# BCD_Counter_1_1.net
KiCad netlist of a schematic drawn in EAGLE
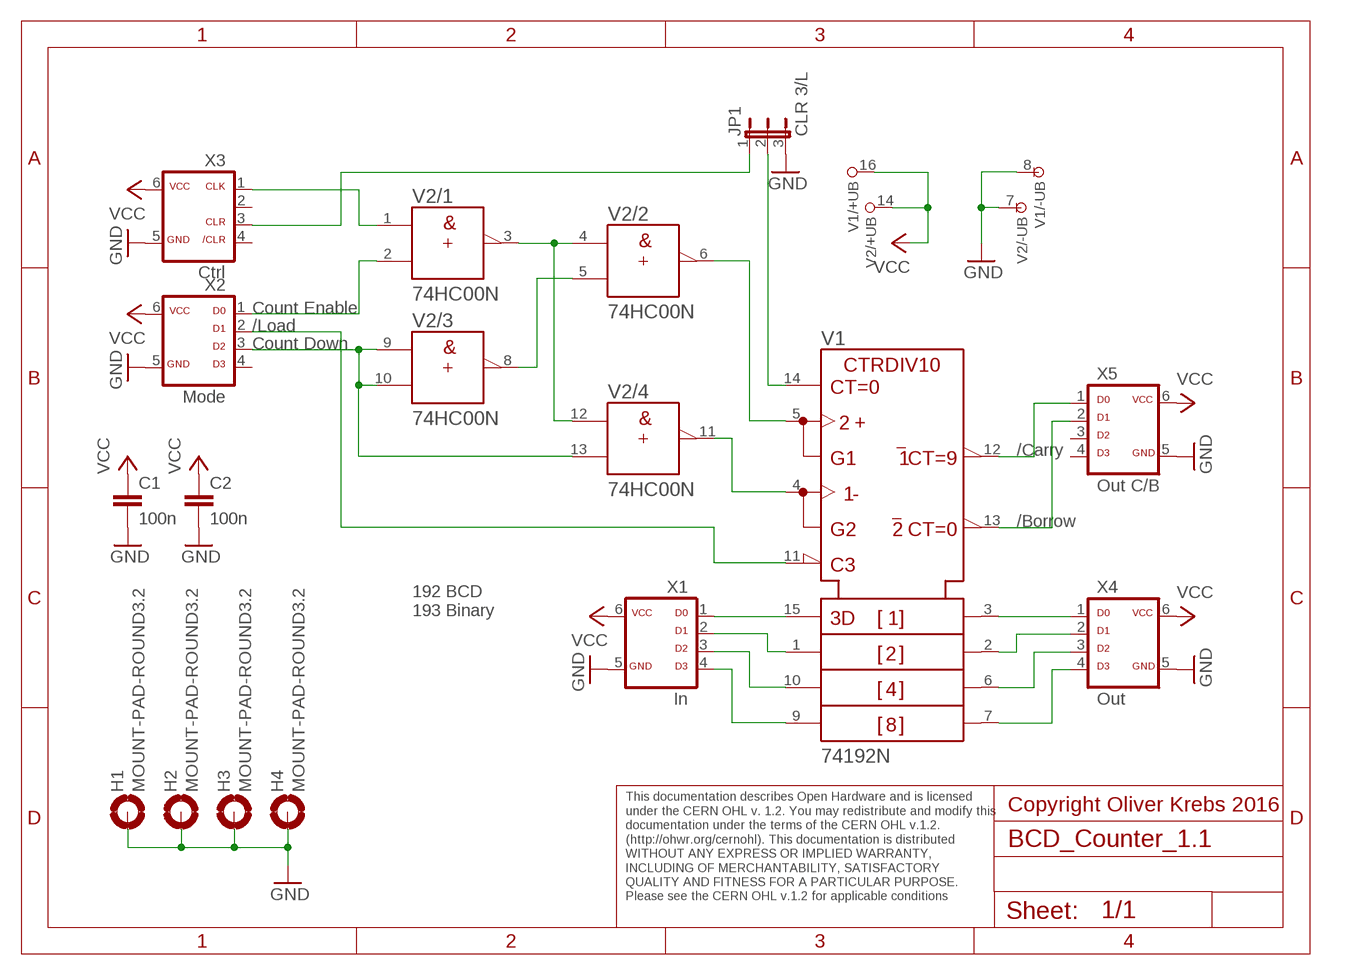
[diagram p0: schematic, sheet 1]

(export (version "E")
  (design (tool "Eeschema 10.0.6"))
  (components
    (comp (ref "C1")
      (value "100n")
      (footprint "eagle-import:C050-025X075")
      (libsource (lib "eagle-import") (part "C-EU050-025X075"))
    )
    (comp (ref "C2")
      (value "100n")
      (footprint "eagle-import:C050-025X075")
      (libsource (lib "eagle-import") (part "C-EU050-025X075"))
    )
    (comp (ref "H1")
      (value "MOUNT-PAD-ROUND3.2")
      (footprint "eagle-import:3,2-PAD")
      (libsource (lib "eagle-import") (part "MOUNT-PAD-ROUND3.2"))
    )
    (comp (ref "H2")
      (value "MOUNT-PAD-ROUND3.2")
      (footprint "eagle-import:3,2-PAD")
      (libsource (lib "eagle-import") (part "MOUNT-PAD-ROUND3.2"))
    )
    (comp (ref "H3")
      (value "MOUNT-PAD-ROUND3.2")
      (footprint "eagle-import:3,2-PAD")
      (libsource (lib "eagle-import") (part "MOUNT-PAD-ROUND3.2"))
    )
    (comp (ref "H4")
      (value "MOUNT-PAD-ROUND3.2")
      (footprint "eagle-import:3,2-PAD")
      (libsource (lib "eagle-import") (part "MOUNT-PAD-ROUND3.2"))
    )
    (comp (ref "JP1")
      (value "CLR 3/L")
      (footprint "eagle-import:JP2")
      (libsource (lib "eagle-import") (part "JP2E"))
    )
    (comp (ref "V1")
      (value "74192N")
      (footprint "eagle-import:DIL16")
      (libsource (lib "eagle-import") (part "74192N"))
    )
    (comp (ref "V2")
      (value "74HC00N")
      (footprint "eagle-import:DIL14")
      (libsource (lib "eagle-import") (part "7400NHC"))
    )
    (comp (ref "X1")
      (value "In")
      (footprint "eagle-import:ML-6")
      (libsource (lib "eagle-import") (part "ML6D"))
    )
    (comp (ref "X2")
      (value "Mode")
      (footprint "eagle-import:ML-6")
      (libsource (lib "eagle-import") (part "ML6D"))
    )
    (comp (ref "X3")
      (value "Ctrl")
      (footprint "eagle-import:ML-6")
      (libsource (lib "eagle-import") (part "ML6C"))
    )
    (comp (ref "X4")
      (value "Out")
      (footprint "eagle-import:ML-6")
      (libsource (lib "eagle-import") (part "ML6D"))
    )
    (comp (ref "X5")
      (value "Out C/B")
      (footprint "eagle-import:ML-6")
      (libsource (lib "eagle-import") (part "ML6D"))
    )
  )
  (nets
    (net (code "1") (name "GND") (class "Default")
      (node (ref "C1") (pin "2") (pinfunction "2_2") (pintype "passive"))
      (node (ref "C2") (pin "2") (pinfunction "2_2") (pintype "passive"))
      (node (ref "H1") (pin "B3,2") (pinfunction "MOUNT_B3,2") (pintype "passive"))
      (node (ref "H2") (pin "B3,2") (pinfunction "MOUNT_B3,2") (pintype "passive"))
      (node (ref "H3") (pin "B3,2") (pinfunction "MOUNT_B3,2") (pintype "passive"))
      (node (ref "H4") (pin "B3,2") (pinfunction "MOUNT_B3,2") (pintype "passive"))
      (node (ref "JP1") (pin "3") (pinfunction "3_3") (pintype "passive"))
      (node (ref "V1") (pin "8") (pinfunction "-UB_8") (pintype "power_in"))
      (node (ref "V2") (pin "7") (pinfunction "-UB_7") (pintype "power_in"))
      (node (ref "X1") (pin "5") (pinfunction "5_5") (pintype "passive"))
      (node (ref "X2") (pin "5") (pinfunction "5_5") (pintype "passive"))
      (node (ref "X3") (pin "5") (pinfunction "5_5") (pintype "passive"))
      (node (ref "X4") (pin "5") (pinfunction "5_5") (pintype "passive"))
      (node (ref "X5") (pin "5") (pinfunction "5_5") (pintype "passive"))
    )
    (net (code "2") (name "Net-(JP1-Pad1)") (class "Default")
      (node (ref "JP1") (pin "1") (pinfunction "1_1") (pintype "passive"))
      (node (ref "X3") (pin "3") (pinfunction "3_3") (pintype "passive"))
    )
    (net (code "3") (name "Net-(V1C-A)") (class "Default")
      (node (ref "V1") (pin "15") (pinfunction "A_15") (pintype "input"))
      (node (ref "X1") (pin "1") (pinfunction "1_1") (pintype "passive"))
    )
    (net (code "4") (name "Net-(V1C-B)") (class "Default")
      (node (ref "V1") (pin "1") (pinfunction "B_1") (pintype "input"))
      (node (ref "X1") (pin "2") (pinfunction "2_2") (pintype "passive"))
    )
    (net (code "5") (name "Net-(V1C-C)") (class "Default")
      (node (ref "V1") (pin "10") (pinfunction "C_10") (pintype "input"))
      (node (ref "X1") (pin "3") (pinfunction "3_3") (pintype "passive"))
    )
    (net (code "6") (name "Net-(V1C-CLR)") (class "Default")
      (node (ref "JP1") (pin "2") (pinfunction "2_2") (pintype "passive"))
      (node (ref "V1") (pin "14") (pinfunction "CLR_14") (pintype "input"))
    )
    (net (code "7") (name "Net-(V1C-D)") (class "Default")
      (node (ref "V1") (pin "9") (pinfunction "D_9") (pintype "input"))
      (node (ref "X1") (pin "4") (pinfunction "4_4") (pintype "passive"))
    )
    (net (code "8") (name "Net-(V1C-DOWN)") (class "Default")
      (node (ref "V1") (pin "4") (pinfunction "DOWN_4") (pintype "input"))
      (node (ref "V2") (pin "11") (pinfunction "Y_11") (pintype "output"))
    )
    (net (code "9") (name "Net-(V1C-QA)") (class "Default")
      (node (ref "V1") (pin "3") (pinfunction "QA_3") (pintype "output"))
      (node (ref "X4") (pin "1") (pinfunction "1_1") (pintype "passive"))
    )
    (net (code "10") (name "Net-(V1C-QB)") (class "Default")
      (node (ref "V1") (pin "2") (pinfunction "QB_2") (pintype "output"))
      (node (ref "X4") (pin "2") (pinfunction "2_2") (pintype "passive"))
    )
    (net (code "11") (name "Net-(V1C-QC)") (class "Default")
      (node (ref "V1") (pin "6") (pinfunction "QC_6") (pintype "output"))
      (node (ref "X4") (pin "3") (pinfunction "3_3") (pintype "passive"))
    )
    (net (code "12") (name "Net-(V1C-QD)") (class "Default")
      (node (ref "V1") (pin "7") (pinfunction "QD_7") (pintype "output"))
      (node (ref "X4") (pin "4") (pinfunction "4_4") (pintype "passive"))
    )
    (net (code "13") (name "Net-(V1C-UP)") (class "Default")
      (node (ref "V1") (pin "5") (pinfunction "UP_5") (pintype "input"))
      (node (ref "V2") (pin "6") (pinfunction "Y_6") (pintype "output"))
    )
    (net (code "14") (name "Net-(V1C-~{BO})") (class "Default")
      (node (ref "V1") (pin "13") (pinfunction "~{BO}_13") (pintype "output"))
      (node (ref "X5") (pin "2") (pinfunction "2_2") (pintype "passive"))
    )
    (net (code "15") (name "Net-(V1C-~{CO})") (class "Default")
      (node (ref "V1") (pin "12") (pinfunction "~{CO}_12") (pintype "output"))
      (node (ref "X5") (pin "1") (pinfunction "1_1") (pintype "passive"))
    )
    (net (code "16") (name "Net-(V1C-~{LOAD})") (class "Default")
      (node (ref "V1") (pin "11") (pinfunction "~{LOAD}_11") (pintype "input"))
      (node (ref "X2") (pin "2") (pinfunction "2_2") (pintype "passive"))
    )
    (net (code "17") (name "Net-(V2C-A)") (class "Default")
      (node (ref "V2") (pin "1") (pinfunction "A_1") (pintype "input"))
      (node (ref "X3") (pin "1") (pinfunction "1_1") (pintype "passive"))
    )
    (net (code "18") (name "Net-(V2C-B)") (class "Default")
      (node (ref "V2") (pin "2") (pinfunction "B_2") (pintype "input"))
      (node (ref "X2") (pin "1") (pinfunction "1_1") (pintype "passive"))
    )
    (net (code "19") (name "Net-(V2C-Y)") (class "Default")
      (node (ref "V2") (pin "12") (pinfunction "A_12") (pintype "input"))
      (node (ref "V2") (pin "3") (pinfunction "Y_3") (pintype "output"))
      (node (ref "V2") (pin "4") (pinfunction "A_4") (pintype "input"))
    )
    (net (code "20") (name "Net-(V2D-B)") (class "Default")
      (node (ref "V2") (pin "5") (pinfunction "B_5") (pintype "input"))
      (node (ref "V2") (pin "8") (pinfunction "Y_8") (pintype "output"))
    )
    (net (code "21") (name "Net-(V2E-A)") (class "Default")
      (node (ref "V2") (pin "10") (pinfunction "B_10") (pintype "input"))
      (node (ref "V2") (pin "13") (pinfunction "B_13") (pintype "input"))
      (node (ref "V2") (pin "9") (pinfunction "A_9") (pintype "input"))
      (node (ref "X2") (pin "3") (pinfunction "3_3") (pintype "passive"))
    )
    (net (code "22") (name "VCC") (class "Default")
      (node (ref "C1") (pin "1") (pinfunction "1_1") (pintype "passive"))
      (node (ref "C2") (pin "1") (pinfunction "1_1") (pintype "passive"))
      (node (ref "V1") (pin "16") (pinfunction "+UB_16") (pintype "power_in"))
      (node (ref "V2") (pin "14") (pinfunction "+UB_14") (pintype "power_in"))
      (node (ref "X1") (pin "6") (pinfunction "6_6") (pintype "passive"))
      (node (ref "X2") (pin "6") (pinfunction "6_6") (pintype "passive"))
      (node (ref "X3") (pin "6") (pinfunction "6_6") (pintype "passive"))
      (node (ref "X4") (pin "6") (pinfunction "6_6") (pintype "passive"))
      (node (ref "X5") (pin "6") (pinfunction "6_6") (pintype "passive"))
    )
    (net (code "23") (name "unconnected-(X2-Pad4)") (class "Default")
      (node (ref "X2") (pin "4") (pinfunction "4_4") (pintype "passive"))
    )
    (net (code "24") (name "unconnected-(X3-Pad2)") (class "Default")
      (node (ref "X3") (pin "2") (pinfunction "2_2") (pintype "passive"))
    )
    (net (code "25") (name "unconnected-(X3-Pad4)") (class "Default")
      (node (ref "X3") (pin "4") (pinfunction "4_4") (pintype "passive"))
    )
    (net (code "26") (name "unconnected-(X5-Pad3)") (class "Default")
      (node (ref "X5") (pin "3") (pinfunction "3_3") (pintype "passive"))
    )
    (net (code "27") (name "unconnected-(X5-Pad4)") (class "Default")
      (node (ref "X5") (pin "4") (pinfunction "4_4") (pintype "passive"))
    )
  )
)
